# waer_level.net
KiCad netlist of a schematic drawn in EAGLE
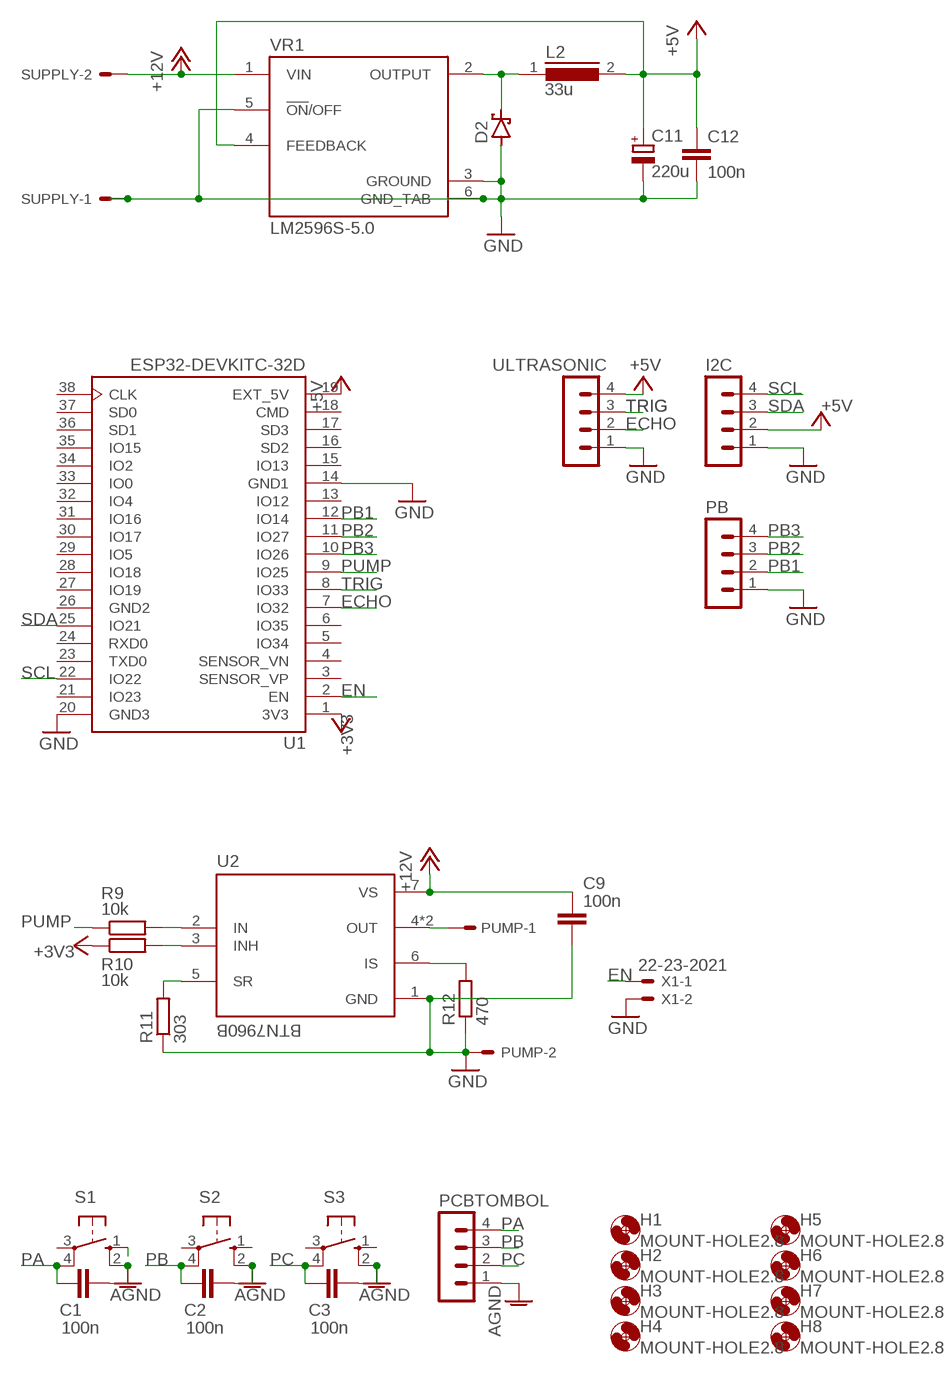
[diagram p0: schematic, sheet 1]

(export (version "E")
  (design (tool "Eeschema 10.0.6"))
  (components
    (comp (ref "C1")
      (value "100n")
      (footprint "eagle-import:C0805")
      (libsource (lib "eagle-import") (part "C-EUC0805"))
    )
    (comp (ref "C2")
      (value "100n")
      (footprint "eagle-import:C0805")
      (libsource (lib "eagle-import") (part "C-EUC0805"))
    )
    (comp (ref "C3")
      (value "100n")
      (footprint "eagle-import:C0805")
      (libsource (lib "eagle-import") (part "C-EUC0805"))
    )
    (comp (ref "C9")
      (value "100n")
      (footprint "eagle-import:C0805")
      (libsource (lib "eagle-import") (part "C-EUC0805"))
    )
    (comp (ref "C11")
      (value "220u")
      (footprint "eagle-import:153CLV-0605")
      (libsource (lib "eagle-import") (part "CPOL-EU153CLV-0605"))
    )
    (comp (ref "C12")
      (value "100n")
      (footprint "eagle-import:C0805")
      (libsource (lib "eagle-import") (part "C-EUC0805"))
    )
    (comp (ref "D2")
      (value "SCHOTTKY-DIODESMD")
      (footprint "eagle-import:SMB")
      (libsource (lib "eagle-import") (part "SCHOTTKY-DIODESMD"))
    )
    (comp (ref "H1")
      (value "MOUNT-HOLE2.8")
      (footprint "eagle-import:2,8")
      (libsource (lib "eagle-import") (part "MOUNT-HOLE2.8"))
    )
    (comp (ref "H2")
      (value "MOUNT-HOLE2.8")
      (footprint "eagle-import:2,8")
      (libsource (lib "eagle-import") (part "MOUNT-HOLE2.8"))
    )
    (comp (ref "H3")
      (value "MOUNT-HOLE2.8")
      (footprint "eagle-import:2,8")
      (libsource (lib "eagle-import") (part "MOUNT-HOLE2.8"))
    )
    (comp (ref "H4")
      (value "MOUNT-HOLE2.8")
      (footprint "eagle-import:2,8")
      (libsource (lib "eagle-import") (part "MOUNT-HOLE2.8"))
    )
    (comp (ref "H5")
      (value "MOUNT-HOLE2.8")
      (footprint "eagle-import:2,8")
      (libsource (lib "eagle-import") (part "MOUNT-HOLE2.8"))
    )
    (comp (ref "H6")
      (value "MOUNT-HOLE2.8")
      (footprint "eagle-import:2,8")
      (libsource (lib "eagle-import") (part "MOUNT-HOLE2.8"))
    )
    (comp (ref "H7")
      (value "MOUNT-HOLE2.8")
      (footprint "eagle-import:2,8")
      (libsource (lib "eagle-import") (part "MOUNT-HOLE2.8"))
    )
    (comp (ref "H8")
      (value "MOUNT-HOLE2.8")
      (footprint "eagle-import:2,8")
      (libsource (lib "eagle-import") (part "MOUNT-HOLE2.8"))
    )
    (comp (ref "I2C")
      (value "MA04-1")
      (footprint "eagle-import:MA04-1")
      (libsource (lib "eagle-import") (part "MA04-1"))
    )
    (comp (ref "L2")
      (value "33u")
      (footprint "eagle-import:DR125")
      (libsource (lib "eagle-import") (part "DR125"))
    )
    (comp (ref "PB")
      (value "MA04-1")
      (footprint "eagle-import:MA04-1")
      (libsource (lib "eagle-import") (part "MA04-1"))
    )
    (comp (ref "PCBTOMBOL")
      (value "MA04-1")
      (footprint "eagle-import:MA04-1")
      (libsource (lib "eagle-import") (part "MA04-1"))
    )
    (comp (ref "PUMP")
      (value "KK-156-2")
      (footprint "eagle-import:KK-156-2")
      (fields (field (name "MF") "MOLEX"))
      (libsource (lib "eagle-import") (part "KK-156-2"))
    )
    (comp (ref "R9")
      (value "10k")
      (footprint "eagle-import:R0805")
      (libsource (lib "eagle-import") (part "R-EU_R0805"))
    )
    (comp (ref "R10")
      (value "10k")
      (footprint "eagle-import:R0805")
      (libsource (lib "eagle-import") (part "R-EU_R0805"))
    )
    (comp (ref "R11")
      (value "303")
      (footprint "eagle-import:R0805")
      (libsource (lib "eagle-import") (part "R-EU_R0805"))
    )
    (comp (ref "R12")
      (value "470")
      (footprint "eagle-import:R0805")
      (libsource (lib "eagle-import") (part "R-EU_R0805"))
    )
    (comp (ref "S1")
      (value "40-XX")
      (footprint "eagle-import:B3F-40XX")
      (fields (field (name "MF") "OMRON COMPONENTS USA") (field (name "MPN") "B3F-4000"))
      (libsource (lib "eagle-import") (part "40-XX"))
    )
    (comp (ref "S2")
      (value "40-XX")
      (footprint "eagle-import:B3F-40XX")
      (fields (field (name "MF") "OMRON COMPONENTS USA") (field (name "MPN") "B3F-4000"))
      (libsource (lib "eagle-import") (part "40-XX"))
    )
    (comp (ref "S3")
      (value "40-XX")
      (footprint "eagle-import:B3F-40XX")
      (fields (field (name "MF") "OMRON COMPONENTS USA") (field (name "MPN") "B3F-4000"))
      (libsource (lib "eagle-import") (part "40-XX"))
    )
    (comp (ref "SUPPLY")
      (value "KK-156-2")
      (footprint "eagle-import:KK-156-2")
      (fields (field (name "MF") "MOLEX"))
      (libsource (lib "eagle-import") (part "KK-156-2"))
    )
    (comp (ref "U1")
      (value "ESP32-DEVKITC-32D")
      (footprint "eagle-import:MODULE_ESP32-DEVKITC-32D")
      (fields (field (name "MF") "Espressif Systems"))
      (libsource (lib "eagle-import") (part "ESP32-DEVKITC-32D"))
    )
    (comp (ref "U2")
      (value "BTN7960B")
      (footprint "eagle-import:IC_BTN7960B")
      (fields (field (name "MF") "Infineon Technologies"))
      (libsource (lib "eagle-import") (part "BTN7960B"))
    )
    (comp (ref "ULTRASONIC")
      (value "MA04-1")
      (footprint "eagle-import:MA04-1")
      (libsource (lib "eagle-import") (part "MA04-1"))
    )
    (comp (ref "VR1")
      (value "LM2596S-5.0")
      (footprint "eagle-import:TO170P1524X483-6N")
      (fields (field (name "MF") "Texas Instruments") (field (name "MP") "LM2596S-5.0/NOPB"))
      (libsource (lib "eagle-import") (part "LM2596S-5.0"))
    )
    (comp (ref "X1")
      (value "22-23-2021")
      (footprint "eagle-import:22-23-2021")
      (fields (field (name "MF") "MOLEX"))
      (libsource (lib "eagle-import") (part "22-23-2021"))
    )
  )
  (nets
    (net (code "1") (name "+3V3") (class "Default")
      (node (ref "R10") (pin "1") (pinfunction "1_1") (pintype "passive"))
      (node (ref "U1") (pin "1") (pinfunction "3V3_1") (pintype "power_in"))
    )
    (net (code "2") (name "+5V") (class "Default")
      (node (ref "C11") (pin "+") (pinfunction "+_+") (pintype "passive"))
      (node (ref "C12") (pin "1") (pinfunction "1_1") (pintype "passive"))
      (node (ref "I2C") (pin "2") (pinfunction "2_2") (pintype "passive"))
      (node (ref "L2") (pin "2") (pinfunction "2_2") (pintype "passive"))
      (node (ref "U1") (pin "19") (pinfunction "EXT_5V_19") (pintype "power_in"))
      (node (ref "ULTRASONIC") (pin "4") (pinfunction "4_4") (pintype "passive"))
      (node (ref "VR1") (pin "4") (pinfunction "FEEDBACK_4") (pintype "input"))
    )
    (net (code "3") (name "+12V") (class "Default")
      (node (ref "C9") (pin "1") (pinfunction "1_1") (pintype "passive"))
      (node (ref "SUPPLY") (pin "2") (pinfunction "S_2") (pintype "passive"))
      (node (ref "U2") (pin "7") (pinfunction "VS_7") (pintype "power_in"))
      (node (ref "VR1") (pin "1") (pinfunction "VIN_1") (pintype "input"))
    )
    (net (code "4") (name "/ECHO") (class "Default")
      (node (ref "U1") (pin "7") (pinfunction "IO32_7") (pintype "bidirectional"))
      (node (ref "ULTRASONIC") (pin "2") (pinfunction "2_2") (pintype "passive"))
    )
    (net (code "5") (name "/EN") (class "Default")
      (node (ref "U1") (pin "2") (pinfunction "EN_2") (pintype "input"))
      (node (ref "X1") (pin "1") (pinfunction "S_1") (pintype "passive"))
    )
    (net (code "6") (name "/GND2") (class "Default")
      (node (ref "U1") (pin "26") (pinfunction "GND2_26") (pintype "power_in"))
    )
    (net (code "7") (name "/PA") (class "Default")
      (node (ref "C1") (pin "1") (pinfunction "1_1") (pintype "passive"))
      (node (ref "PCBTOMBOL") (pin "4") (pinfunction "4_4") (pintype "passive"))
      (node (ref "S1") (pin "4") (pinfunction "P1_4") (pintype "passive"))
    )
    (net (code "8") (name "/PB") (class "Default")
      (node (ref "C2") (pin "1") (pinfunction "1_1") (pintype "passive"))
      (node (ref "PCBTOMBOL") (pin "3") (pinfunction "3_3") (pintype "passive"))
      (node (ref "S2") (pin "4") (pinfunction "P1_4") (pintype "passive"))
    )
    (net (code "9") (name "/PB1") (class "Default")
      (node (ref "PB") (pin "2") (pinfunction "2_2") (pintype "passive"))
      (node (ref "U1") (pin "12") (pinfunction "IO14_12") (pintype "bidirectional"))
    )
    (net (code "10") (name "/PB2") (class "Default")
      (node (ref "PB") (pin "3") (pinfunction "3_3") (pintype "passive"))
      (node (ref "U1") (pin "11") (pinfunction "IO27_11") (pintype "bidirectional"))
    )
    (net (code "11") (name "/PB3") (class "Default")
      (node (ref "PB") (pin "4") (pinfunction "4_4") (pintype "passive"))
      (node (ref "U1") (pin "10") (pinfunction "IO26_10") (pintype "bidirectional"))
    )
    (net (code "12") (name "/PC") (class "Default")
      (node (ref "C3") (pin "1") (pinfunction "1_1") (pintype "passive"))
      (node (ref "PCBTOMBOL") (pin "2") (pinfunction "2_2") (pintype "passive"))
      (node (ref "S3") (pin "4") (pinfunction "P1_4") (pintype "passive"))
    )
    (net (code "13") (name "/PUMP") (class "Default")
      (node (ref "R9") (pin "1") (pinfunction "1_1") (pintype "passive"))
      (node (ref "U1") (pin "9") (pinfunction "IO25_9") (pintype "bidirectional"))
    )
    (net (code "14") (name "/SCL") (class "Default")
      (node (ref "I2C") (pin "4") (pinfunction "4_4") (pintype "passive"))
      (node (ref "U1") (pin "22") (pinfunction "IO22_22") (pintype "bidirectional"))
    )
    (net (code "15") (name "/SDA") (class "Default")
      (node (ref "I2C") (pin "3") (pinfunction "3_3") (pintype "passive"))
      (node (ref "U1") (pin "25") (pinfunction "IO21_25") (pintype "bidirectional"))
    )
    (net (code "16") (name "/TRIG") (class "Default")
      (node (ref "U1") (pin "8") (pinfunction "IO33_8") (pintype "bidirectional"))
      (node (ref "ULTRASONIC") (pin "3") (pinfunction "3_3") (pintype "passive"))
    )
    (net (code "17") (name "AGND") (class "Default")
      (node (ref "C1") (pin "2") (pinfunction "2_2") (pintype "passive"))
      (node (ref "C2") (pin "2") (pinfunction "2_2") (pintype "passive"))
      (node (ref "C3") (pin "2") (pinfunction "2_2") (pintype "passive"))
      (node (ref "PCBTOMBOL") (pin "1") (pinfunction "1_1") (pintype "passive"))
      (node (ref "S1") (pin "2") (pinfunction "S1_2") (pintype "passive"))
      (node (ref "S2") (pin "2") (pinfunction "S1_2") (pintype "passive"))
      (node (ref "S3") (pin "2") (pinfunction "S1_2") (pintype "passive"))
    )
    (net (code "18") (name "GND") (class "Default")
      (node (ref "C11") (pin "-") (pinfunction "-_-") (pintype "passive"))
      (node (ref "C12") (pin "2") (pinfunction "2_2") (pintype "passive"))
      (node (ref "C9") (pin "2") (pinfunction "2_2") (pintype "passive"))
      (node (ref "D2") (pin "A") (pinfunction "A_A") (pintype "passive"))
      (node (ref "I2C") (pin "1") (pinfunction "1_1") (pintype "passive"))
      (node (ref "PB") (pin "1") (pinfunction "1_1") (pintype "passive"))
      (node (ref "PUMP") (pin "2") (pinfunction "S_2") (pintype "passive"))
      (node (ref "R11") (pin "1") (pinfunction "1_1") (pintype "passive"))
      (node (ref "R12") (pin "1") (pinfunction "1_1") (pintype "passive"))
      (node (ref "SUPPLY") (pin "1") (pinfunction "S_1") (pintype "passive"))
      (node (ref "U1") (pin "14") (pinfunction "GND1_14") (pintype "power_in"))
      (node (ref "U1") (pin "20") (pinfunction "GND3_20") (pintype "power_in"))
      (node (ref "U2") (pin "1") (pinfunction "GND_1") (pintype "power_in"))
      (node (ref "ULTRASONIC") (pin "1") (pinfunction "1_1") (pintype "passive"))
      (node (ref "VR1") (pin "3") (pinfunction "GROUND_3") (pintype "power_in"))
      (node (ref "VR1") (pin "5") (pinfunction "~{ON}/OFF_5") (pintype "input"))
      (node (ref "VR1") (pin "6") (pinfunction "GND_TAB_6") (pintype "power_in"))
      (node (ref "X1") (pin "2") (pinfunction "S_2") (pintype "passive"))
    )
    (net (code "19") (name "Net-(PUMPA-S)") (class "Default")
      (node (ref "PUMP") (pin "1") (pinfunction "S_1") (pintype "passive"))
      (node (ref "U2") (pin "4") (pinfunction "OUT_4") (pintype "output"))
      (node (ref "U2") (pin "8") (pinfunction "OUT_8") (pintype "output"))
    )
    (net (code "20") (name "Net-(U2-IN)") (class "Default")
      (node (ref "R9") (pin "2") (pinfunction "2_2") (pintype "passive"))
      (node (ref "U2") (pin "2") (pinfunction "IN_2") (pintype "input"))
    )
    (net (code "21") (name "Net-(U2-INH)") (class "Default")
      (node (ref "R10") (pin "2") (pinfunction "2_2") (pintype "passive"))
      (node (ref "U2") (pin "3") (pinfunction "INH_3") (pintype "input"))
    )
    (net (code "22") (name "Net-(U2-IS)") (class "Default")
      (node (ref "R12") (pin "2") (pinfunction "2_2") (pintype "passive"))
      (node (ref "U2") (pin "6") (pinfunction "IS_6") (pintype "output"))
    )
    (net (code "23") (name "Net-(U2-SR)") (class "Default")
      (node (ref "R11") (pin "2") (pinfunction "2_2") (pintype "passive"))
      (node (ref "U2") (pin "5") (pinfunction "SR_5") (pintype "input"))
    )
    (net (code "24") (name "Net-(VR1-OUTPUT)") (class "Default")
      (node (ref "D2") (pin "C") (pinfunction "C_C") (pintype "passive"))
      (node (ref "L2") (pin "1") (pinfunction "1_1") (pintype "passive"))
      (node (ref "VR1") (pin "2") (pinfunction "OUTPUT_2") (pintype "output"))
    )
    (net (code "25") (name "unconnected-(S1-P-Pad3)") (class "Default")
      (node (ref "S1") (pin "3") (pinfunction "P_3") (pintype "passive"))
    )
    (net (code "26") (name "unconnected-(S1-S-Pad1)") (class "Default")
      (node (ref "S1") (pin "1") (pinfunction "S_1") (pintype "passive"))
    )
    (net (code "27") (name "unconnected-(S2-P-Pad3)") (class "Default")
      (node (ref "S2") (pin "3") (pinfunction "P_3") (pintype "passive"))
    )
    (net (code "28") (name "unconnected-(S2-S-Pad1)") (class "Default")
      (node (ref "S2") (pin "1") (pinfunction "S_1") (pintype "passive"))
    )
    (net (code "29") (name "unconnected-(S3-P-Pad3)") (class "Default")
      (node (ref "S3") (pin "3") (pinfunction "P_3") (pintype "passive"))
    )
    (net (code "30") (name "unconnected-(S3-S-Pad1)") (class "Default")
      (node (ref "S3") (pin "1") (pinfunction "S_1") (pintype "passive"))
    )
    (net (code "31") (name "unconnected-(U1-CLK-Pad38)") (class "Default")
      (node (ref "U1") (pin "38") (pinfunction "CLK_38") (pintype "input"))
    )
    (net (code "32") (name "unconnected-(U1-CMD-Pad18)") (class "Default")
      (node (ref "U1") (pin "18") (pinfunction "CMD_18") (pintype "bidirectional"))
    )
    (net (code "33") (name "unconnected-(U1-IO0-Pad33)") (class "Default")
      (node (ref "U1") (pin "33") (pinfunction "IO0_33") (pintype "bidirectional"))
    )
    (net (code "34") (name "unconnected-(U1-IO2-Pad34)") (class "Default")
      (node (ref "U1") (pin "34") (pinfunction "IO2_34") (pintype "bidirectional"))
    )
    (net (code "35") (name "unconnected-(U1-IO4-Pad32)") (class "Default")
      (node (ref "U1") (pin "32") (pinfunction "IO4_32") (pintype "bidirectional"))
    )
    (net (code "36") (name "unconnected-(U1-IO5-Pad29)") (class "Default")
      (node (ref "U1") (pin "29") (pinfunction "IO5_29") (pintype "bidirectional"))
    )
    (net (code "37") (name "unconnected-(U1-IO12-Pad13)") (class "Default")
      (node (ref "U1") (pin "13") (pinfunction "IO12_13") (pintype "bidirectional"))
    )
    (net (code "38") (name "unconnected-(U1-IO13-Pad15)") (class "Default")
      (node (ref "U1") (pin "15") (pinfunction "IO13_15") (pintype "bidirectional"))
    )
    (net (code "39") (name "unconnected-(U1-IO15-Pad35)") (class "Default")
      (node (ref "U1") (pin "35") (pinfunction "IO15_35") (pintype "bidirectional"))
    )
    (net (code "40") (name "unconnected-(U1-IO16-Pad31)") (class "Default")
      (node (ref "U1") (pin "31") (pinfunction "IO16_31") (pintype "bidirectional"))
    )
    (net (code "41") (name "unconnected-(U1-IO17-Pad30)") (class "Default")
      (node (ref "U1") (pin "30") (pinfunction "IO17_30") (pintype "bidirectional"))
    )
    (net (code "42") (name "unconnected-(U1-IO18-Pad28)") (class "Default")
      (node (ref "U1") (pin "28") (pinfunction "IO18_28") (pintype "bidirectional"))
    )
    (net (code "43") (name "unconnected-(U1-IO19-Pad27)") (class "Default")
      (node (ref "U1") (pin "27") (pinfunction "IO19_27") (pintype "bidirectional"))
    )
    (net (code "44") (name "unconnected-(U1-IO23-Pad21)") (class "Default")
      (node (ref "U1") (pin "21") (pinfunction "IO23_21") (pintype "bidirectional"))
    )
    (net (code "45") (name "unconnected-(U1-IO34-Pad5)") (class "Default")
      (node (ref "U1") (pin "5") (pinfunction "IO34_5") (pintype "bidirectional"))
    )
    (net (code "46") (name "unconnected-(U1-IO35-Pad6)") (class "Default")
      (node (ref "U1") (pin "6") (pinfunction "IO35_6") (pintype "bidirectional"))
    )
    (net (code "47") (name "unconnected-(U1-RXD0-Pad24)") (class "Default")
      (node (ref "U1") (pin "24") (pinfunction "RXD0_24") (pintype "input"))
    )
    (net (code "48") (name "unconnected-(U1-SD0-Pad37)") (class "Default")
      (node (ref "U1") (pin "37") (pinfunction "SD0_37") (pintype "bidirectional"))
    )
    (net (code "49") (name "unconnected-(U1-SD1-Pad36)") (class "Default")
      (node (ref "U1") (pin "36") (pinfunction "SD1_36") (pintype "bidirectional"))
    )
    (net (code "50") (name "unconnected-(U1-SD2-Pad16)") (class "Default")
      (node (ref "U1") (pin "16") (pinfunction "SD2_16") (pintype "bidirectional"))
    )
    (net (code "51") (name "unconnected-(U1-SD3-Pad17)") (class "Default")
      (node (ref "U1") (pin "17") (pinfunction "SD3_17") (pintype "bidirectional"))
    )
    (net (code "52") (name "unconnected-(U1-SENSOR_VN-Pad4)") (class "Default")
      (node (ref "U1") (pin "4") (pinfunction "SENSOR_VN_4") (pintype "input"))
    )
    (net (code "53") (name "unconnected-(U1-SENSOR_VP-Pad3)") (class "Default")
      (node (ref "U1") (pin "3") (pinfunction "SENSOR_VP_3") (pintype "input"))
    )
    (net (code "54") (name "unconnected-(U1-TXD0-Pad23)") (class "Default")
      (node (ref "U1") (pin "23") (pinfunction "TXD0_23") (pintype "output"))
    )
  )
)
